# Breadboard.net
KiCad netlist of a schematic drawn in EAGLE
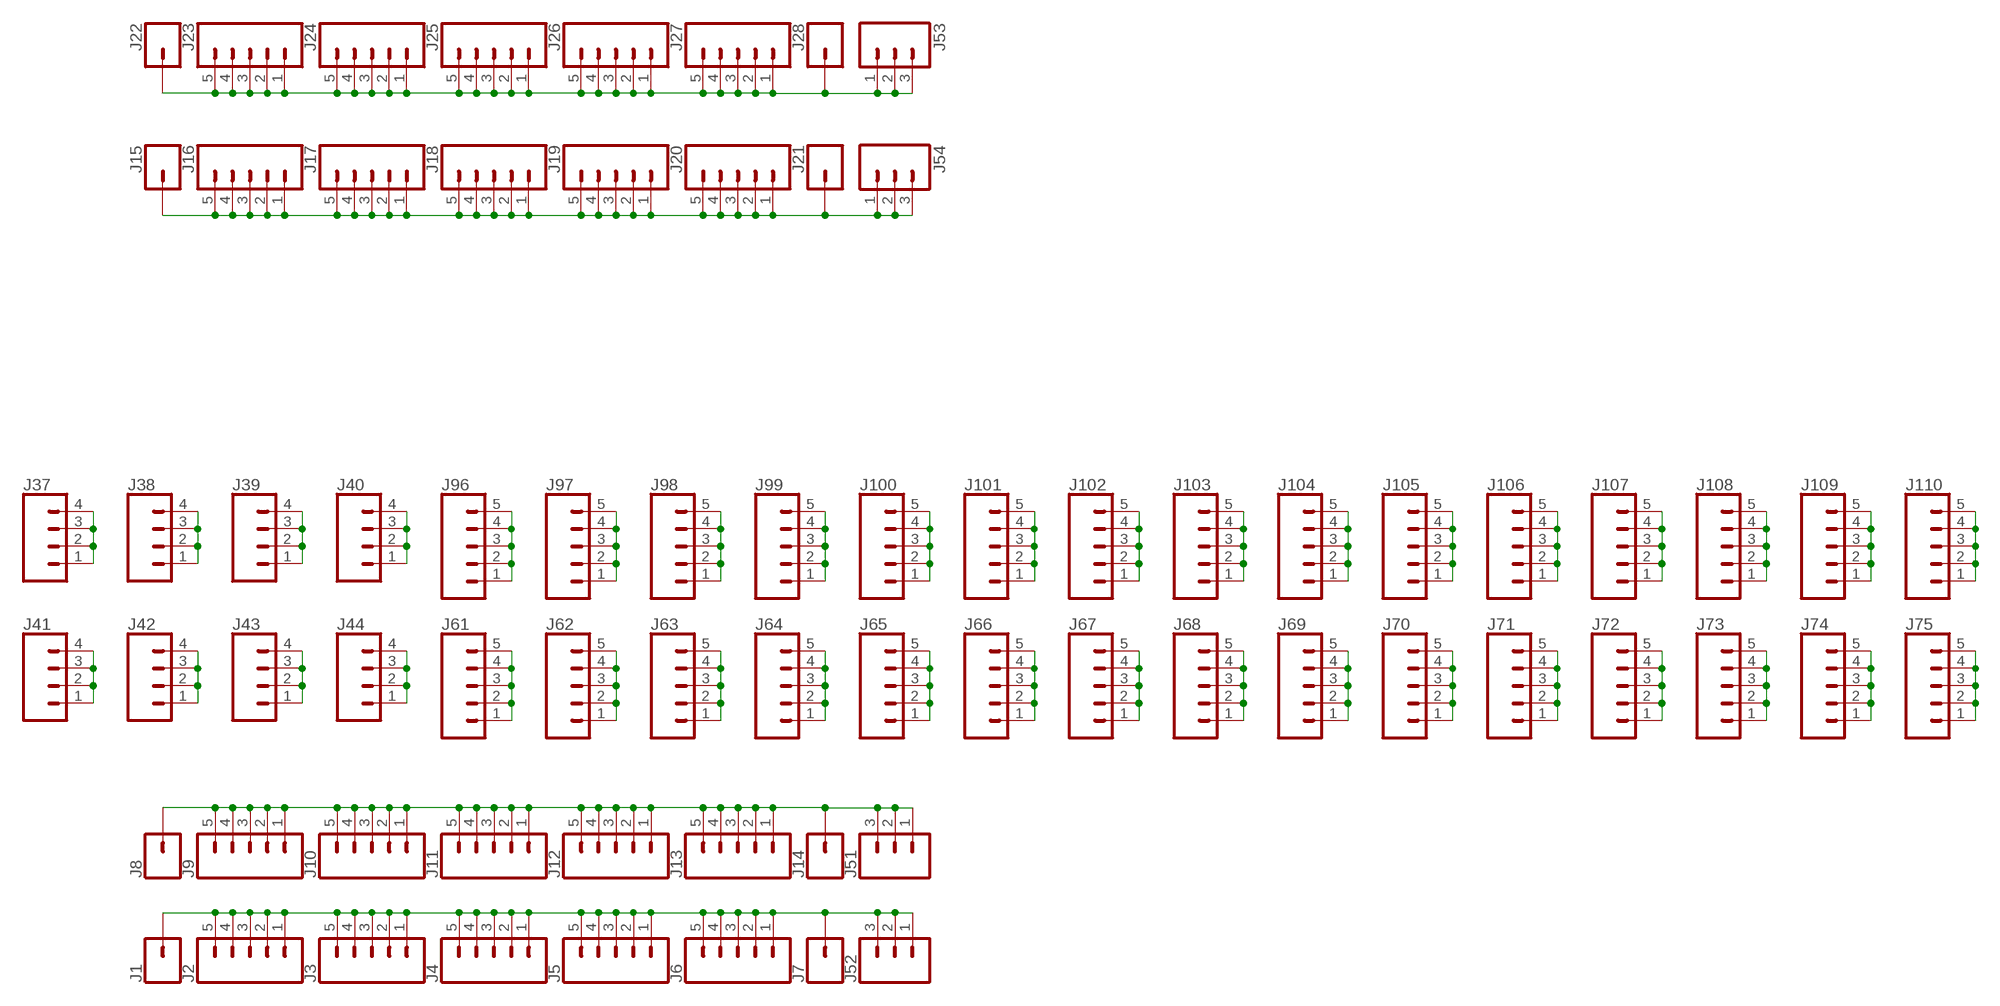
[diagram p0: schematic, sheet 1, part 1 of 2]
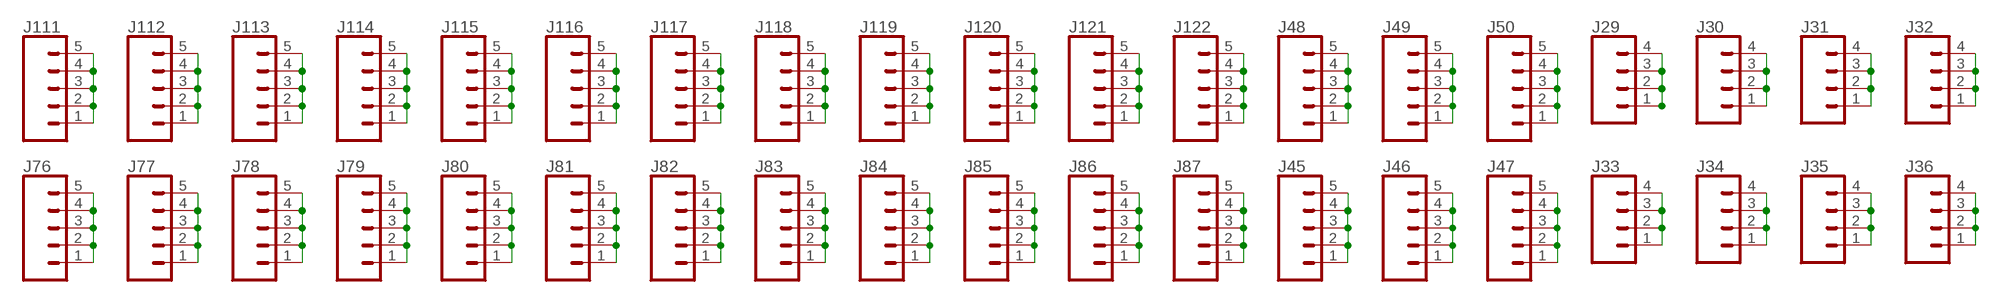
[diagram p1: schematic, sheet 1, part 2 of 2]

(export (version "E")
  (design (tool "Eeschema 10.0.6"))
  (components
    (comp (ref "J1")
      (value "CONN_01")
      (footprint "eagle-import:1X01")
      (libsource (lib "eagle-import") (part "CONN_01"))
    )
    (comp (ref "J2")
      (value "CONN_05")
      (footprint "eagle-import:1X05")
      (libsource (lib "eagle-import") (part "CONN_05"))
    )
    (comp (ref "J3")
      (value "CONN_05")
      (footprint "eagle-import:1X05")
      (libsource (lib "eagle-import") (part "CONN_05"))
    )
    (comp (ref "J4")
      (value "CONN_05")
      (footprint "eagle-import:1X05")
      (libsource (lib "eagle-import") (part "CONN_05"))
    )
    (comp (ref "J5")
      (value "CONN_05")
      (footprint "eagle-import:1X05")
      (libsource (lib "eagle-import") (part "CONN_05"))
    )
    (comp (ref "J6")
      (value "CONN_05")
      (footprint "eagle-import:1X05")
      (libsource (lib "eagle-import") (part "CONN_05"))
    )
    (comp (ref "J7")
      (value "CONN_01")
      (footprint "eagle-import:1X01")
      (libsource (lib "eagle-import") (part "CONN_01"))
    )
    (comp (ref "J8")
      (value "CONN_01")
      (footprint "eagle-import:1X01")
      (libsource (lib "eagle-import") (part "CONN_01"))
    )
    (comp (ref "J9")
      (value "CONN_05")
      (footprint "eagle-import:1X05")
      (libsource (lib "eagle-import") (part "CONN_05"))
    )
    (comp (ref "J10")
      (value "CONN_05")
      (footprint "eagle-import:1X05")
      (libsource (lib "eagle-import") (part "CONN_05"))
    )
    (comp (ref "J11")
      (value "CONN_05")
      (footprint "eagle-import:1X05")
      (libsource (lib "eagle-import") (part "CONN_05"))
    )
    (comp (ref "J12")
      (value "CONN_05")
      (footprint "eagle-import:1X05")
      (libsource (lib "eagle-import") (part "CONN_05"))
    )
    (comp (ref "J13")
      (value "CONN_05")
      (footprint "eagle-import:1X05")
      (libsource (lib "eagle-import") (part "CONN_05"))
    )
    (comp (ref "J14")
      (value "CONN_01")
      (footprint "eagle-import:1X01")
      (libsource (lib "eagle-import") (part "CONN_01"))
    )
    (comp (ref "J15")
      (value "CONN_01")
      (footprint "eagle-import:1X01")
      (libsource (lib "eagle-import") (part "CONN_01"))
    )
    (comp (ref "J16")
      (value "CONN_05")
      (footprint "eagle-import:1X05")
      (libsource (lib "eagle-import") (part "CONN_05"))
    )
    (comp (ref "J17")
      (value "CONN_05")
      (footprint "eagle-import:1X05")
      (libsource (lib "eagle-import") (part "CONN_05"))
    )
    (comp (ref "J18")
      (value "CONN_05")
      (footprint "eagle-import:1X05")
      (libsource (lib "eagle-import") (part "CONN_05"))
    )
    (comp (ref "J19")
      (value "CONN_05")
      (footprint "eagle-import:1X05")
      (libsource (lib "eagle-import") (part "CONN_05"))
    )
    (comp (ref "J20")
      (value "CONN_05")
      (footprint "eagle-import:1X05")
      (libsource (lib "eagle-import") (part "CONN_05"))
    )
    (comp (ref "J21")
      (value "CONN_01")
      (footprint "eagle-import:1X01")
      (libsource (lib "eagle-import") (part "CONN_01"))
    )
    (comp (ref "J22")
      (value "CONN_01")
      (footprint "eagle-import:1X01")
      (libsource (lib "eagle-import") (part "CONN_01"))
    )
    (comp (ref "J23")
      (value "CONN_05")
      (footprint "eagle-import:1X05")
      (libsource (lib "eagle-import") (part "CONN_05"))
    )
    (comp (ref "J24")
      (value "CONN_05")
      (footprint "eagle-import:1X05")
      (libsource (lib "eagle-import") (part "CONN_05"))
    )
    (comp (ref "J25")
      (value "CONN_05")
      (footprint "eagle-import:1X05")
      (libsource (lib "eagle-import") (part "CONN_05"))
    )
    (comp (ref "J26")
      (value "CONN_05")
      (footprint "eagle-import:1X05")
      (libsource (lib "eagle-import") (part "CONN_05"))
    )
    (comp (ref "J27")
      (value "CONN_05")
      (footprint "eagle-import:1X05")
      (libsource (lib "eagle-import") (part "CONN_05"))
    )
    (comp (ref "J28")
      (value "CONN_01")
      (footprint "eagle-import:1X01")
      (libsource (lib "eagle-import") (part "CONN_01"))
    )
    (comp (ref "J29")
      (value "CONN_04PTH")
      (footprint "eagle-import:1X04")
      (libsource (lib "eagle-import") (part "CONN_04PTH"))
    )
    (comp (ref "J30")
      (value "CONN_04PTH")
      (footprint "eagle-import:1X04")
      (libsource (lib "eagle-import") (part "CONN_04PTH"))
    )
    (comp (ref "J31")
      (value "CONN_04PTH")
      (footprint "eagle-import:1X04")
      (libsource (lib "eagle-import") (part "CONN_04PTH"))
    )
    (comp (ref "J32")
      (value "CONN_04PTH")
      (footprint "eagle-import:1X04")
      (libsource (lib "eagle-import") (part "CONN_04PTH"))
    )
    (comp (ref "J33")
      (value "CONN_04PTH")
      (footprint "eagle-import:1X04")
      (libsource (lib "eagle-import") (part "CONN_04PTH"))
    )
    (comp (ref "J34")
      (value "CONN_04PTH")
      (footprint "eagle-import:1X04")
      (libsource (lib "eagle-import") (part "CONN_04PTH"))
    )
    (comp (ref "J35")
      (value "CONN_04PTH")
      (footprint "eagle-import:1X04")
      (libsource (lib "eagle-import") (part "CONN_04PTH"))
    )
    (comp (ref "J36")
      (value "CONN_04PTH")
      (footprint "eagle-import:1X04")
      (libsource (lib "eagle-import") (part "CONN_04PTH"))
    )
    (comp (ref "J37")
      (value "CONN_04PTH")
      (footprint "eagle-import:1X04")
      (libsource (lib "eagle-import") (part "CONN_04PTH"))
    )
    (comp (ref "J38")
      (value "CONN_04PTH")
      (footprint "eagle-import:1X04")
      (libsource (lib "eagle-import") (part "CONN_04PTH"))
    )
    (comp (ref "J39")
      (value "CONN_04PTH")
      (footprint "eagle-import:1X04")
      (libsource (lib "eagle-import") (part "CONN_04PTH"))
    )
    (comp (ref "J40")
      (value "CONN_04PTH")
      (footprint "eagle-import:1X04")
      (libsource (lib "eagle-import") (part "CONN_04PTH"))
    )
    (comp (ref "J41")
      (value "CONN_04PTH")
      (footprint "eagle-import:1X04")
      (libsource (lib "eagle-import") (part "CONN_04PTH"))
    )
    (comp (ref "J42")
      (value "CONN_04PTH")
      (footprint "eagle-import:1X04")
      (libsource (lib "eagle-import") (part "CONN_04PTH"))
    )
    (comp (ref "J43")
      (value "CONN_04PTH")
      (footprint "eagle-import:1X04")
      (libsource (lib "eagle-import") (part "CONN_04PTH"))
    )
    (comp (ref "J44")
      (value "CONN_04PTH")
      (footprint "eagle-import:1X04")
      (libsource (lib "eagle-import") (part "CONN_04PTH"))
    )
    (comp (ref "J45")
      (value "CONN_05")
      (footprint "eagle-import:1X05")
      (libsource (lib "eagle-import") (part "CONN_05"))
    )
    (comp (ref "J46")
      (value "CONN_05")
      (footprint "eagle-import:1X05")
      (libsource (lib "eagle-import") (part "CONN_05"))
    )
    (comp (ref "J47")
      (value "CONN_05")
      (footprint "eagle-import:1X05")
      (libsource (lib "eagle-import") (part "CONN_05"))
    )
    (comp (ref "J48")
      (value "CONN_05")
      (footprint "eagle-import:1X05")
      (libsource (lib "eagle-import") (part "CONN_05"))
    )
    (comp (ref "J49")
      (value "CONN_05")
      (footprint "eagle-import:1X05")
      (libsource (lib "eagle-import") (part "CONN_05"))
    )
    (comp (ref "J50")
      (value "CONN_05")
      (footprint "eagle-import:1X05")
      (libsource (lib "eagle-import") (part "CONN_05"))
    )
    (comp (ref "J51")
      (value "455-1750-1-ND")
      (footprint "eagle-import:1X03")
      (libsource (lib "eagle-import") (part "CONN_03"))
    )
    (comp (ref "J52")
      (value "455-1750-1-ND")
      (footprint "eagle-import:1X03")
      (libsource (lib "eagle-import") (part "CONN_03"))
    )
    (comp (ref "J53")
      (value "455-1750-1-ND")
      (footprint "eagle-import:1X03")
      (libsource (lib "eagle-import") (part "CONN_03"))
    )
    (comp (ref "J54")
      (value "455-1750-1-ND")
      (footprint "eagle-import:1X03")
      (libsource (lib "eagle-import") (part "CONN_03"))
    )
    (comp (ref "J61")
      (value "CONN_05")
      (footprint "eagle-import:1X05")
      (libsource (lib "eagle-import") (part "CONN_05"))
    )
    (comp (ref "J62")
      (value "CONN_05")
      (footprint "eagle-import:1X05")
      (libsource (lib "eagle-import") (part "CONN_05"))
    )
    (comp (ref "J63")
      (value "CONN_05")
      (footprint "eagle-import:1X05")
      (libsource (lib "eagle-import") (part "CONN_05"))
    )
    (comp (ref "J64")
      (value "CONN_05")
      (footprint "eagle-import:1X05")
      (libsource (lib "eagle-import") (part "CONN_05"))
    )
    (comp (ref "J65")
      (value "CONN_05")
      (footprint "eagle-import:1X05")
      (libsource (lib "eagle-import") (part "CONN_05"))
    )
    (comp (ref "J66")
      (value "CONN_05")
      (footprint "eagle-import:1X05")
      (libsource (lib "eagle-import") (part "CONN_05"))
    )
    (comp (ref "J67")
      (value "CONN_05")
      (footprint "eagle-import:1X05")
      (libsource (lib "eagle-import") (part "CONN_05"))
    )
    (comp (ref "J68")
      (value "CONN_05")
      (footprint "eagle-import:1X05")
      (libsource (lib "eagle-import") (part "CONN_05"))
    )
    (comp (ref "J69")
      (value "CONN_05")
      (footprint "eagle-import:1X05")
      (libsource (lib "eagle-import") (part "CONN_05"))
    )
    (comp (ref "J70")
      (value "CONN_05")
      (footprint "eagle-import:1X05")
      (libsource (lib "eagle-import") (part "CONN_05"))
    )
    (comp (ref "J71")
      (value "CONN_05")
      (footprint "eagle-import:1X05")
      (libsource (lib "eagle-import") (part "CONN_05"))
    )
    (comp (ref "J72")
      (value "CONN_05")
      (footprint "eagle-import:1X05")
      (libsource (lib "eagle-import") (part "CONN_05"))
    )
    (comp (ref "J73")
      (value "CONN_05")
      (footprint "eagle-import:1X05")
      (libsource (lib "eagle-import") (part "CONN_05"))
    )
    (comp (ref "J74")
      (value "CONN_05")
      (footprint "eagle-import:1X05")
      (libsource (lib "eagle-import") (part "CONN_05"))
    )
    (comp (ref "J75")
      (value "CONN_05")
      (footprint "eagle-import:1X05")
      (libsource (lib "eagle-import") (part "CONN_05"))
    )
    (comp (ref "J76")
      (value "CONN_05")
      (footprint "eagle-import:1X05")
      (libsource (lib "eagle-import") (part "CONN_05"))
    )
    (comp (ref "J77")
      (value "CONN_05")
      (footprint "eagle-import:1X05")
      (libsource (lib "eagle-import") (part "CONN_05"))
    )
    (comp (ref "J78")
      (value "CONN_05")
      (footprint "eagle-import:1X05")
      (libsource (lib "eagle-import") (part "CONN_05"))
    )
    (comp (ref "J79")
      (value "CONN_05")
      (footprint "eagle-import:1X05")
      (libsource (lib "eagle-import") (part "CONN_05"))
    )
    (comp (ref "J80")
      (value "CONN_05")
      (footprint "eagle-import:1X05")
      (libsource (lib "eagle-import") (part "CONN_05"))
    )
    (comp (ref "J81")
      (value "CONN_05")
      (footprint "eagle-import:1X05")
      (libsource (lib "eagle-import") (part "CONN_05"))
    )
    (comp (ref "J82")
      (value "CONN_05")
      (footprint "eagle-import:1X05")
      (libsource (lib "eagle-import") (part "CONN_05"))
    )
    (comp (ref "J83")
      (value "CONN_05")
      (footprint "eagle-import:1X05")
      (libsource (lib "eagle-import") (part "CONN_05"))
    )
    (comp (ref "J84")
      (value "CONN_05")
      (footprint "eagle-import:1X05")
      (libsource (lib "eagle-import") (part "CONN_05"))
    )
    (comp (ref "J85")
      (value "CONN_05")
      (footprint "eagle-import:1X05")
      (libsource (lib "eagle-import") (part "CONN_05"))
    )
    (comp (ref "J86")
      (value "CONN_05")
      (footprint "eagle-import:1X05")
      (libsource (lib "eagle-import") (part "CONN_05"))
    )
    (comp (ref "J87")
      (value "CONN_05")
      (footprint "eagle-import:1X05")
      (libsource (lib "eagle-import") (part "CONN_05"))
    )
    (comp (ref "J96")
      (value "CONN_05")
      (footprint "eagle-import:1X05")
      (libsource (lib "eagle-import") (part "CONN_05"))
    )
    (comp (ref "J97")
      (value "CONN_05")
      (footprint "eagle-import:1X05")
      (libsource (lib "eagle-import") (part "CONN_05"))
    )
    (comp (ref "J98")
      (value "CONN_05")
      (footprint "eagle-import:1X05")
      (libsource (lib "eagle-import") (part "CONN_05"))
    )
    (comp (ref "J99")
      (value "CONN_05")
      (footprint "eagle-import:1X05")
      (libsource (lib "eagle-import") (part "CONN_05"))
    )
    (comp (ref "J100")
      (value "CONN_05")
      (footprint "eagle-import:1X05")
      (libsource (lib "eagle-import") (part "CONN_05"))
    )
    (comp (ref "J101")
      (value "CONN_05")
      (footprint "eagle-import:1X05")
      (libsource (lib "eagle-import") (part "CONN_05"))
    )
    (comp (ref "J102")
      (value "CONN_05")
      (footprint "eagle-import:1X05")
      (libsource (lib "eagle-import") (part "CONN_05"))
    )
    (comp (ref "J103")
      (value "CONN_05")
      (footprint "eagle-import:1X05")
      (libsource (lib "eagle-import") (part "CONN_05"))
    )
    (comp (ref "J104")
      (value "CONN_05")
      (footprint "eagle-import:1X05")
      (libsource (lib "eagle-import") (part "CONN_05"))
    )
    (comp (ref "J105")
      (value "CONN_05")
      (footprint "eagle-import:1X05")
      (libsource (lib "eagle-import") (part "CONN_05"))
    )
    (comp (ref "J106")
      (value "CONN_05")
      (footprint "eagle-import:1X05")
      (libsource (lib "eagle-import") (part "CONN_05"))
    )
    (comp (ref "J107")
      (value "CONN_05")
      (footprint "eagle-import:1X05")
      (libsource (lib "eagle-import") (part "CONN_05"))
    )
    (comp (ref "J108")
      (value "CONN_05")
      (footprint "eagle-import:1X05")
      (libsource (lib "eagle-import") (part "CONN_05"))
    )
    (comp (ref "J109")
      (value "CONN_05")
      (footprint "eagle-import:1X05")
      (libsource (lib "eagle-import") (part "CONN_05"))
    )
    (comp (ref "J110")
      (value "CONN_05")
      (footprint "eagle-import:1X05")
      (libsource (lib "eagle-import") (part "CONN_05"))
    )
    (comp (ref "J111")
      (value "CONN_05")
      (footprint "eagle-import:1X05")
      (libsource (lib "eagle-import") (part "CONN_05"))
    )
    (comp (ref "J112")
      (value "CONN_05")
      (footprint "eagle-import:1X05")
      (libsource (lib "eagle-import") (part "CONN_05"))
    )
    (comp (ref "J113")
      (value "CONN_05")
      (footprint "eagle-import:1X05")
      (libsource (lib "eagle-import") (part "CONN_05"))
    )
    (comp (ref "J114")
      (value "CONN_05")
      (footprint "eagle-import:1X05")
      (libsource (lib "eagle-import") (part "CONN_05"))
    )
    (comp (ref "J115")
      (value "CONN_05")
      (footprint "eagle-import:1X05")
      (libsource (lib "eagle-import") (part "CONN_05"))
    )
    (comp (ref "J116")
      (value "CONN_05")
      (footprint "eagle-import:1X05")
      (libsource (lib "eagle-import") (part "CONN_05"))
    )
    (comp (ref "J117")
      (value "CONN_05")
      (footprint "eagle-import:1X05")
      (libsource (lib "eagle-import") (part "CONN_05"))
    )
    (comp (ref "J118")
      (value "CONN_05")
      (footprint "eagle-import:1X05")
      (libsource (lib "eagle-import") (part "CONN_05"))
    )
    (comp (ref "J119")
      (value "CONN_05")
      (footprint "eagle-import:1X05")
      (libsource (lib "eagle-import") (part "CONN_05"))
    )
    (comp (ref "J120")
      (value "CONN_05")
      (footprint "eagle-import:1X05")
      (libsource (lib "eagle-import") (part "CONN_05"))
    )
    (comp (ref "J121")
      (value "CONN_05")
      (footprint "eagle-import:1X05")
      (libsource (lib "eagle-import") (part "CONN_05"))
    )
    (comp (ref "J122")
      (value "CONN_05")
      (footprint "eagle-import:1X05")
      (libsource (lib "eagle-import") (part "CONN_05"))
    )
  )
  (nets
    (net (code "1") (name "Net-(J1-Pad1)") (class "Default")
      (node (ref "J1") (pin "1") (pinfunction "1_1") (pintype "passive"))
      (node (ref "J2") (pin "1") (pinfunction "1_1") (pintype "passive"))
      (node (ref "J2") (pin "2") (pinfunction "2_2") (pintype "passive"))
      (node (ref "J2") (pin "3") (pinfunction "3_3") (pintype "passive"))
      (node (ref "J2") (pin "4") (pinfunction "4_4") (pintype "passive"))
      (node (ref "J2") (pin "5") (pinfunction "5_5") (pintype "passive"))
      (node (ref "J3") (pin "1") (pinfunction "1_1") (pintype "passive"))
      (node (ref "J3") (pin "2") (pinfunction "2_2") (pintype "passive"))
      (node (ref "J3") (pin "3") (pinfunction "3_3") (pintype "passive"))
      (node (ref "J3") (pin "4") (pinfunction "4_4") (pintype "passive"))
      (node (ref "J3") (pin "5") (pinfunction "5_5") (pintype "passive"))
      (node (ref "J4") (pin "1") (pinfunction "1_1") (pintype "passive"))
      (node (ref "J4") (pin "2") (pinfunction "2_2") (pintype "passive"))
      (node (ref "J4") (pin "3") (pinfunction "3_3") (pintype "passive"))
      (node (ref "J4") (pin "4") (pinfunction "4_4") (pintype "passive"))
      (node (ref "J4") (pin "5") (pinfunction "5_5") (pintype "passive"))
      (node (ref "J5") (pin "1") (pinfunction "1_1") (pintype "passive"))
      (node (ref "J5") (pin "2") (pinfunction "2_2") (pintype "passive"))
      (node (ref "J5") (pin "3") (pinfunction "3_3") (pintype "passive"))
      (node (ref "J5") (pin "4") (pinfunction "4_4") (pintype "passive"))
      (node (ref "J5") (pin "5") (pinfunction "5_5") (pintype "passive"))
      (node (ref "J52") (pin "1") (pinfunction "1_1") (pintype "passive"))
      (node (ref "J52") (pin "2") (pinfunction "2_2") (pintype "passive"))
      (node (ref "J52") (pin "3") (pinfunction "3_3") (pintype "passive"))
      (node (ref "J6") (pin "1") (pinfunction "1_1") (pintype "passive"))
      (node (ref "J6") (pin "2") (pinfunction "2_2") (pintype "passive"))
      (node (ref "J6") (pin "3") (pinfunction "3_3") (pintype "passive"))
      (node (ref "J6") (pin "4") (pinfunction "4_4") (pintype "passive"))
      (node (ref "J6") (pin "5") (pinfunction "5_5") (pintype "passive"))
      (node (ref "J7") (pin "1") (pinfunction "1_1") (pintype "passive"))
    )
    (net (code "2") (name "Net-(J10-Pad1)") (class "Default")
      (node (ref "J10") (pin "1") (pinfunction "1_1") (pintype "passive"))
      (node (ref "J10") (pin "2") (pinfunction "2_2") (pintype "passive"))
      (node (ref "J10") (pin "3") (pinfunction "3_3") (pintype "passive"))
      (node (ref "J10") (pin "4") (pinfunction "4_4") (pintype "passive"))
      (node (ref "J10") (pin "5") (pinfunction "5_5") (pintype "passive"))
      (node (ref "J11") (pin "1") (pinfunction "1_1") (pintype "passive"))
      (node (ref "J11") (pin "2") (pinfunction "2_2") (pintype "passive"))
      (node (ref "J11") (pin "3") (pinfunction "3_3") (pintype "passive"))
      (node (ref "J11") (pin "4") (pinfunction "4_4") (pintype "passive"))
      (node (ref "J11") (pin "5") (pinfunction "5_5") (pintype "passive"))
      (node (ref "J12") (pin "1") (pinfunction "1_1") (pintype "passive"))
      (node (ref "J12") (pin "2") (pinfunction "2_2") (pintype "passive"))
      (node (ref "J12") (pin "3") (pinfunction "3_3") (pintype "passive"))
      (node (ref "J12") (pin "4") (pinfunction "4_4") (pintype "passive"))
      (node (ref "J12") (pin "5") (pinfunction "5_5") (pintype "passive"))
      (node (ref "J13") (pin "1") (pinfunction "1_1") (pintype "passive"))
      (node (ref "J13") (pin "2") (pinfunction "2_2") (pintype "passive"))
      (node (ref "J13") (pin "3") (pinfunction "3_3") (pintype "passive"))
      (node (ref "J13") (pin "4") (pinfunction "4_4") (pintype "passive"))
      (node (ref "J13") (pin "5") (pinfunction "5_5") (pintype "passive"))
      (node (ref "J14") (pin "1") (pinfunction "1_1") (pintype "passive"))
      (node (ref "J51") (pin "1") (pinfunction "1_1") (pintype "passive"))
      (node (ref "J51") (pin "2") (pinfunction "2_2") (pintype "passive"))
      (node (ref "J51") (pin "3") (pinfunction "3_3") (pintype "passive"))
      (node (ref "J8") (pin "1") (pinfunction "1_1") (pintype "passive"))
      (node (ref "J9") (pin "1") (pinfunction "1_1") (pintype "passive"))
      (node (ref "J9") (pin "2") (pinfunction "2_2") (pintype "passive"))
      (node (ref "J9") (pin "3") (pinfunction "3_3") (pintype "passive"))
      (node (ref "J9") (pin "4") (pinfunction "4_4") (pintype "passive"))
      (node (ref "J9") (pin "5") (pinfunction "5_5") (pintype "passive"))
    )
    (net (code "3") (name "Net-(J15-Pad1)") (class "Default")
      (node (ref "J15") (pin "1") (pinfunction "1_1") (pintype "passive"))
      (node (ref "J16") (pin "1") (pinfunction "1_1") (pintype "passive"))
      (node (ref "J16") (pin "2") (pinfunction "2_2") (pintype "passive"))
      (node (ref "J16") (pin "3") (pinfunction "3_3") (pintype "passive"))
      (node (ref "J16") (pin "4") (pinfunction "4_4") (pintype "passive"))
      (node (ref "J16") (pin "5") (pinfunction "5_5") (pintype "passive"))
      (node (ref "J17") (pin "1") (pinfunction "1_1") (pintype "passive"))
      (node (ref "J17") (pin "2") (pinfunction "2_2") (pintype "passive"))
      (node (ref "J17") (pin "3") (pinfunction "3_3") (pintype "passive"))
      (node (ref "J17") (pin "4") (pinfunction "4_4") (pintype "passive"))
      (node (ref "J17") (pin "5") (pinfunction "5_5") (pintype "passive"))
      (node (ref "J18") (pin "1") (pinfunction "1_1") (pintype "passive"))
      (node (ref "J18") (pin "2") (pinfunction "2_2") (pintype "passive"))
      (node (ref "J18") (pin "3") (pinfunction "3_3") (pintype "passive"))
      (node (ref "J18") (pin "4") (pinfunction "4_4") (pintype "passive"))
      (node (ref "J18") (pin "5") (pinfunction "5_5") (pintype "passive"))
      (node (ref "J19") (pin "1") (pinfunction "1_1") (pintype "passive"))
      (node (ref "J19") (pin "2") (pinfunction "2_2") (pintype "passive"))
      (node (ref "J19") (pin "3") (pinfunction "3_3") (pintype "passive"))
      (node (ref "J19") (pin "4") (pinfunction "4_4") (pintype "passive"))
      (node (ref "J19") (pin "5") (pinfunction "5_5") (pintype "passive"))
      (node (ref "J20") (pin "1") (pinfunction "1_1") (pintype "passive"))
      (node (ref "J20") (pin "2") (pinfunction "2_2") (pintype "passive"))
      (node (ref "J20") (pin "3") (pinfunction "3_3") (pintype "passive"))
      (node (ref "J20") (pin "4") (pinfunction "4_4") (pintype "passive"))
      (node (ref "J20") (pin "5") (pinfunction "5_5") (pintype "passive"))
      (node (ref "J21") (pin "1") (pinfunction "1_1") (pintype "passive"))
      (node (ref "J54") (pin "1") (pinfunction "1_1") (pintype "passive"))
      (node (ref "J54") (pin "2") (pinfunction "2_2") (pintype "passive"))
      (node (ref "J54") (pin "3") (pinfunction "3_3") (pintype "passive"))
    )
    (net (code "4") (name "Net-(J22-Pad1)") (class "Default")
      (node (ref "J22") (pin "1") (pinfunction "1_1") (pintype "passive"))
      (node (ref "J23") (pin "1") (pinfunction "1_1") (pintype "passive"))
      (node (ref "J23") (pin "2") (pinfunction "2_2") (pintype "passive"))
      (node (ref "J23") (pin "3") (pinfunction "3_3") (pintype "passive"))
      (node (ref "J23") (pin "4") (pinfunction "4_4") (pintype "passive"))
      (node (ref "J23") (pin "5") (pinfunction "5_5") (pintype "passive"))
      (node (ref "J24") (pin "1") (pinfunction "1_1") (pintype "passive"))
      (node (ref "J24") (pin "2") (pinfunction "2_2") (pintype "passive"))
      (node (ref "J24") (pin "3") (pinfunction "3_3") (pintype "passive"))
      (node (ref "J24") (pin "4") (pinfunction "4_4") (pintype "passive"))
      (node (ref "J24") (pin "5") (pinfunction "5_5") (pintype "passive"))
      (node (ref "J25") (pin "1") (pinfunction "1_1") (pintype "passive"))
      (node (ref "J25") (pin "2") (pinfunction "2_2") (pintype "passive"))
      (node (ref "J25") (pin "3") (pinfunction "3_3") (pintype "passive"))
      (node (ref "J25") (pin "4") (pinfunction "4_4") (pintype "passive"))
      (node (ref "J25") (pin "5") (pinfunction "5_5") (pintype "passive"))
      (node (ref "J26") (pin "1") (pinfunction "1_1") (pintype "passive"))
      (node (ref "J26") (pin "2") (pinfunction "2_2") (pintype "passive"))
      (node (ref "J26") (pin "3") (pinfunction "3_3") (pintype "passive"))
      (node (ref "J26") (pin "4") (pinfunction "4_4") (pintype "passive"))
      (node (ref "J26") (pin "5") (pinfunction "5_5") (pintype "passive"))
      (node (ref "J27") (pin "1") (pinfunction "1_1") (pintype "passive"))
      (node (ref "J27") (pin "2") (pinfunction "2_2") (pintype "passive"))
      (node (ref "J27") (pin "3") (pinfunction "3_3") (pintype "passive"))
      (node (ref "J27") (pin "4") (pinfunction "4_4") (pintype "passive"))
      (node (ref "J27") (pin "5") (pinfunction "5_5") (pintype "passive"))
      (node (ref "J28") (pin "1") (pinfunction "1_1") (pintype "passive"))
      (node (ref "J53") (pin "1") (pinfunction "1_1") (pintype "passive"))
      (node (ref "J53") (pin "2") (pinfunction "2_2") (pintype "passive"))
      (node (ref "J53") (pin "3") (pinfunction "3_3") (pintype "passive"))
    )
    (net (code "5") (name "Net-(J29-Pad1)") (class "Default")
      (node (ref "J29") (pin "1") (pinfunction "1_1") (pintype "passive"))
      (node (ref "J29") (pin "2") (pinfunction "2_2") (pintype "passive"))
      (node (ref "J29") (pin "3") (pinfunction "3_3") (pintype "passive"))
      (node (ref "J29") (pin "4") (pinfunction "4_4") (pintype "passive"))
    )
    (net (code "6") (name "Net-(J30-Pad1)") (class "Default")
      (node (ref "J30") (pin "1") (pinfunction "1_1") (pintype "passive"))
      (node (ref "J30") (pin "2") (pinfunction "2_2") (pintype "passive"))
      (node (ref "J30") (pin "3") (pinfunction "3_3") (pintype "passive"))
      (node (ref "J30") (pin "4") (pinfunction "4_4") (pintype "passive"))
    )
    (net (code "7") (name "Net-(J31-Pad1)") (class "Default")
      (node (ref "J31") (pin "1") (pinfunction "1_1") (pintype "passive"))
      (node (ref "J31") (pin "2") (pinfunction "2_2") (pintype "passive"))
      (node (ref "J31") (pin "3") (pinfunction "3_3") (pintype "passive"))
      (node (ref "J31") (pin "4") (pinfunction "4_4") (pintype "passive"))
    )
    (net (code "8") (name "Net-(J32-Pad1)") (class "Default")
      (node (ref "J32") (pin "1") (pinfunction "1_1") (pintype "passive"))
      (node (ref "J32") (pin "2") (pinfunction "2_2") (pintype "passive"))
      (node (ref "J32") (pin "3") (pinfunction "3_3") (pintype "passive"))
      (node (ref "J32") (pin "4") (pinfunction "4_4") (pintype "passive"))
    )
    (net (code "9") (name "Net-(J33-Pad1)") (class "Default")
      (node (ref "J33") (pin "1") (pinfunction "1_1") (pintype "passive"))
      (node (ref "J33") (pin "2") (pinfunction "2_2") (pintype "passive"))
      (node (ref "J33") (pin "3") (pinfunction "3_3") (pintype "passive"))
      (node (ref "J33") (pin "4") (pinfunction "4_4") (pintype "passive"))
    )
    (net (code "10") (name "Net-(J34-Pad1)") (class "Default")
      (node (ref "J34") (pin "1") (pinfunction "1_1") (pintype "passive"))
      (node (ref "J34") (pin "2") (pinfunction "2_2") (pintype "passive"))
      (node (ref "J34") (pin "3") (pinfunction "3_3") (pintype "passive"))
      (node (ref "J34") (pin "4") (pinfunction "4_4") (pintype "passive"))
    )
    (net (code "11") (name "Net-(J35-Pad1)") (class "Default")
      (node (ref "J35") (pin "1") (pinfunction "1_1") (pintype "passive"))
      (node (ref "J35") (pin "2") (pinfunction "2_2") (pintype "passive"))
      (node (ref "J35") (pin "3") (pinfunction "3_3") (pintype "passive"))
      (node (ref "J35") (pin "4") (pinfunction "4_4") (pintype "passive"))
    )
    (net (code "12") (name "Net-(J36-Pad1)") (class "Default")
      (node (ref "J36") (pin "1") (pinfunction "1_1") (pintype "passive"))
      (node (ref "J36") (pin "2") (pinfunction "2_2") (pintype "passive"))
      (node (ref "J36") (pin "3") (pinfunction "3_3") (pintype "passive"))
      (node (ref "J36") (pin "4") (pinfunction "4_4") (pintype "passive"))
    )
    (net (code "13") (name "Net-(J37-Pad1)") (class "Default")
      (node (ref "J37") (pin "1") (pinfunction "1_1") (pintype "passive"))
      (node (ref "J37") (pin "2") (pinfunction "2_2") (pintype "passive"))
      (node (ref "J37") (pin "3") (pinfunction "3_3") (pintype "passive"))
      (node (ref "J37") (pin "4") (pinfunction "4_4") (pintype "passive"))
    )
    (net (code "14") (name "Net-(J38-Pad1)") (class "Default")
      (node (ref "J38") (pin "1") (pinfunction "1_1") (pintype "passive"))
      (node (ref "J38") (pin "2") (pinfunction "2_2") (pintype "passive"))
      (node (ref "J38") (pin "3") (pinfunction "3_3") (pintype "passive"))
      (node (ref "J38") (pin "4") (pinfunction "4_4") (pintype "passive"))
    )
    (net (code "15") (name "Net-(J39-Pad1)") (class "Default")
      (node (ref "J39") (pin "1") (pinfunction "1_1") (pintype "passive"))
      (node (ref "J39") (pin "2") (pinfunction "2_2") (pintype "passive"))
      (node (ref "J39") (pin "3") (pinfunction "3_3") (pintype "passive"))
      (node (ref "J39") (pin "4") (pinfunction "4_4") (pintype "passive"))
    )
    (net (code "16") (name "Net-(J40-Pad1)") (class "Default")
      (node (ref "J40") (pin "1") (pinfunction "1_1") (pintype "passive"))
      (node (ref "J40") (pin "2") (pinfunction "2_2") (pintype "passive"))
      (node (ref "J40") (pin "3") (pinfunction "3_3") (pintype "passive"))
      (node (ref "J40") (pin "4") (pinfunction "4_4") (pintype "passive"))
    )
    (net (code "17") (name "Net-(J41-Pad1)") (class "Default")
      (node (ref "J41") (pin "1") (pinfunction "1_1") (pintype "passive"))
      (node (ref "J41") (pin "2") (pinfunction "2_2") (pintype "passive"))
      (node (ref "J41") (pin "3") (pinfunction "3_3") (pintype "passive"))
      (node (ref "J41") (pin "4") (pinfunction "4_4") (pintype "passive"))
    )
    (net (code "18") (name "Net-(J42-Pad1)") (class "Default")
      (node (ref "J42") (pin "1") (pinfunction "1_1") (pintype "passive"))
      (node (ref "J42") (pin "2") (pinfunction "2_2") (pintype "passive"))
      (node (ref "J42") (pin "3") (pinfunction "3_3") (pintype "passive"))
      (node (ref "J42") (pin "4") (pinfunction "4_4") (pintype "passive"))
    )
    (net (code "19") (name "Net-(J43-Pad1)") (class "Default")
      (node (ref "J43") (pin "1") (pinfunction "1_1") (pintype "passive"))
      (node (ref "J43") (pin "2") (pinfunction "2_2") (pintype "passive"))
      (node (ref "J43") (pin "3") (pinfunction "3_3") (pintype "passive"))
      (node (ref "J43") (pin "4") (pinfunction "4_4") (pintype "passive"))
    )
    (net (code "20") (name "Net-(J44-Pad1)") (class "Default")
      (node (ref "J44") (pin "1") (pinfunction "1_1") (pintype "passive"))
      (node (ref "J44") (pin "2") (pinfunction "2_2") (pintype "passive"))
      (node (ref "J44") (pin "3") (pinfunction "3_3") (pintype "passive"))
      (node (ref "J44") (pin "4") (pinfunction "4_4") (pintype "passive"))
    )
    (net (code "21") (name "Net-(J45-Pad1)") (class "Default")
      (node (ref "J45") (pin "1") (pinfunction "1_1") (pintype "passive"))
      (node (ref "J45") (pin "2") (pinfunction "2_2") (pintype "passive"))
      (node (ref "J45") (pin "3") (pinfunction "3_3") (pintype "passive"))
      (node (ref "J45") (pin "4") (pinfunction "4_4") (pintype "passive"))
      (node (ref "J45") (pin "5") (pinfunction "5_5") (pintype "passive"))
    )
    (net (code "22") (name "Net-(J46-Pad1)") (class "Default")
      (node (ref "J46") (pin "1") (pinfunction "1_1") (pintype "passive"))
      (node (ref "J46") (pin "2") (pinfunction "2_2") (pintype "passive"))
      (node (ref "J46") (pin "3") (pinfunction "3_3") (pintype "passive"))
      (node (ref "J46") (pin "4") (pinfunction "4_4") (pintype "passive"))
      (node (ref "J46") (pin "5") (pinfunction "5_5") (pintype "passive"))
    )
    (net (code "23") (name "Net-(J47-Pad1)") (class "Default")
      (node (ref "J47") (pin "1") (pinfunction "1_1") (pintype "passive"))
      (node (ref "J47") (pin "2") (pinfunction "2_2") (pintype "passive"))
      (node (ref "J47") (pin "3") (pinfunction "3_3") (pintype "passive"))
      (node (ref "J47") (pin "4") (pinfunction "4_4") (pintype "passive"))
      (node (ref "J47") (pin "5") (pinfunction "5_5") (pintype "passive"))
    )
    (net (code "24") (name "Net-(J48-Pad1)") (class "Default")
      (node (ref "J48") (pin "1") (pinfunction "1_1") (pintype "passive"))
      (node (ref "J48") (pin "2") (pinfunction "2_2") (pintype "passive"))
      (node (ref "J48") (pin "3") (pinfunction "3_3") (pintype "passive"))
      (node (ref "J48") (pin "4") (pinfunction "4_4") (pintype "passive"))
      (node (ref "J48") (pin "5") (pinfunction "5_5") (pintype "passive"))
    )
    (net (code "25") (name "Net-(J49-Pad1)") (class "Default")
      (node (ref "J49") (pin "1") (pinfunction "1_1") (pintype "passive"))
      (node (ref "J49") (pin "2") (pinfunction "2_2") (pintype "passive"))
      (node (ref "J49") (pin "3") (pinfunction "3_3") (pintype "passive"))
      (node (ref "J49") (pin "4") (pinfunction "4_4") (pintype "passive"))
      (node (ref "J49") (pin "5") (pinfunction "5_5") (pintype "passive"))
    )
    (net (code "26") (name "Net-(J50-Pad1)") (class "Default")
      (node (ref "J50") (pin "1") (pinfunction "1_1") (pintype "passive"))
      (node (ref "J50") (pin "2") (pinfunction "2_2") (pintype "passive"))
      (node (ref "J50") (pin "3") (pinfunction "3_3") (pintype "passive"))
      (node (ref "J50") (pin "4") (pinfunction "4_4") (pintype "passive"))
      (node (ref "J50") (pin "5") (pinfunction "5_5") (pintype "passive"))
    )
    (net (code "27") (name "Net-(J61-Pad1)") (class "Default")
      (node (ref "J61") (pin "1") (pinfunction "1_1") (pintype "passive"))
      (node (ref "J61") (pin "2") (pinfunction "2_2") (pintype "passive"))
      (node (ref "J61") (pin "3") (pinfunction "3_3") (pintype "passive"))
      (node (ref "J61") (pin "4") (pinfunction "4_4") (pintype "passive"))
      (node (ref "J61") (pin "5") (pinfunction "5_5") (pintype "passive"))
    )
    (net (code "28") (name "Net-(J62-Pad1)") (class "Default")
      (node (ref "J62") (pin "1") (pinfunction "1_1") (pintype "passive"))
      (node (ref "J62") (pin "2") (pinfunction "2_2") (pintype "passive"))
      (node (ref "J62") (pin "3") (pinfunction "3_3") (pintype "passive"))
      (node (ref "J62") (pin "4") (pinfunction "4_4") (pintype "passive"))
      (node (ref "J62") (pin "5") (pinfunction "5_5") (pintype "passive"))
    )
    (net (code "29") (name "Net-(J63-Pad1)") (class "Default")
      (node (ref "J63") (pin "1") (pinfunction "1_1") (pintype "passive"))
      (node (ref "J63") (pin "2") (pinfunction "2_2") (pintype "passive"))
      (node (ref "J63") (pin "3") (pinfunction "3_3") (pintype "passive"))
      (node (ref "J63") (pin "4") (pinfunction "4_4") (pintype "passive"))
      (node (ref "J63") (pin "5") (pinfunction "5_5") (pintype "passive"))
    )
    (net (code "30") (name "Net-(J64-Pad1)") (class "Default")
      (node (ref "J64") (pin "1") (pinfunction "1_1") (pintype "passive"))
      (node (ref "J64") (pin "2") (pinfunction "2_2") (pintype "passive"))
      (node (ref "J64") (pin "3") (pinfunction "3_3") (pintype "passive"))
      (node (ref "J64") (pin "4") (pinfunction "4_4") (pintype "passive"))
      (node (ref "J64") (pin "5") (pinfunction "5_5") (pintype "passive"))
    )
    (net (code "31") (name "Net-(J65-Pad1)") (class "Default")
      (node (ref "J65") (pin "1") (pinfunction "1_1") (pintype "passive"))
      (node (ref "J65") (pin "2") (pinfunction "2_2") (pintype "passive"))
      (node (ref "J65") (pin "3") (pinfunction "3_3") (pintype "passive"))
      (node (ref "J65") (pin "4") (pinfunction "4_4") (pintype "passive"))
      (node (ref "J65") (pin "5") (pinfunction "5_5") (pintype "passive"))
    )
    (net (code "32") (name "Net-(J66-Pad1)") (class "Default")
      (node (ref "J66") (pin "1") (pinfunction "1_1") (pintype "passive"))
      (node (ref "J66") (pin "2") (pinfunction "2_2") (pintype "passive"))
      (node (ref "J66") (pin "3") (pinfunction "3_3") (pintype "passive"))
      (node (ref "J66") (pin "4") (pinfunction "4_4") (pintype "passive"))
      (node (ref "J66") (pin "5") (pinfunction "5_5") (pintype "passive"))
    )
    (net (code "33") (name "Net-(J67-Pad1)") (class "Default")
      (node (ref "J67") (pin "1") (pinfunction "1_1") (pintype "passive"))
      (node (ref "J67") (pin "2") (pinfunction "2_2") (pintype "passive"))
      (node (ref "J67") (pin "3") (pinfunction "3_3") (pintype "passive"))
      (node (ref "J67") (pin "4") (pinfunction "4_4") (pintype "passive"))
      (node (ref "J67") (pin "5") (pinfunction "5_5") (pintype "passive"))
    )
    (net (code "34") (name "Net-(J68-Pad1)") (class "Default")
      (node (ref "J68") (pin "1") (pinfunction "1_1") (pintype "passive"))
      (node (ref "J68") (pin "2") (pinfunction "2_2") (pintype "passive"))
      (node (ref "J68") (pin "3") (pinfunction "3_3") (pintype "passive"))
      (node (ref "J68") (pin "4") (pinfunction "4_4") (pintype "passive"))
      (node (ref "J68") (pin "5") (pinfunction "5_5") (pintype "passive"))
    )
    (net (code "35") (name "Net-(J69-Pad1)") (class "Default")
      (node (ref "J69") (pin "1") (pinfunction "1_1") (pintype "passive"))
      (node (ref "J69") (pin "2") (pinfunction "2_2") (pintype "passive"))
      (node (ref "J69") (pin "3") (pinfunction "3_3") (pintype "passive"))
      (node (ref "J69") (pin "4") (pinfunction "4_4") (pintype "passive"))
      (node (ref "J69") (pin "5") (pinfunction "5_5") (pintype "passive"))
    )
    (net (code "36") (name "Net-(J70-Pad1)") (class "Default")
      (node (ref "J70") (pin "1") (pinfunction "1_1") (pintype "passive"))
      (node (ref "J70") (pin "2") (pinfunction "2_2") (pintype "passive"))
      (node (ref "J70") (pin "3") (pinfunction "3_3") (pintype "passive"))
      (node (ref "J70") (pin "4") (pinfunction "4_4") (pintype "passive"))
      (node (ref "J70") (pin "5") (pinfunction "5_5") (pintype "passive"))
    )
    (net (code "37") (name "Net-(J71-Pad1)") (class "Default")
      (node (ref "J71") (pin "1") (pinfunction "1_1") (pintype "passive"))
      (node (ref "J71") (pin "2") (pinfunction "2_2") (pintype "passive"))
      (node (ref "J71") (pin "3") (pinfunction "3_3") (pintype "passive"))
      (node (ref "J71") (pin "4") (pinfunction "4_4") (pintype "passive"))
      (node (ref "J71") (pin "5") (pinfunction "5_5") (pintype "passive"))
    )
    (net (code "38") (name "Net-(J72-Pad1)") (class "Default")
      (node (ref "J72") (pin "1") (pinfunction "1_1") (pintype "passive"))
      (node (ref "J72") (pin "2") (pinfunction "2_2") (pintype "passive"))
      (node (ref "J72") (pin "3") (pinfunction "3_3") (pintype "passive"))
      (node (ref "J72") (pin "4") (pinfunction "4_4") (pintype "passive"))
      (node (ref "J72") (pin "5") (pinfunction "5_5") (pintype "passive"))
    )
    (net (code "39") (name "Net-(J73-Pad1)") (class "Default")
      (node (ref "J73") (pin "1") (pinfunction "1_1") (pintype "passive"))
      (node (ref "J73") (pin "2") (pinfunction "2_2") (pintype "passive"))
      (node (ref "J73") (pin "3") (pinfunction "3_3") (pintype "passive"))
      (node (ref "J73") (pin "4") (pinfunction "4_4") (pintype "passive"))
      (node (ref "J73") (pin "5") (pinfunction "5_5") (pintype "passive"))
    )
    (net (code "40") (name "Net-(J74-Pad1)") (class "Default")
      (node (ref "J74") (pin "1") (pinfunction "1_1") (pintype "passive"))
      (node (ref "J74") (pin "2") (pinfunction "2_2") (pintype "passive"))
      (node (ref "J74") (pin "3") (pinfunction "3_3") (pintype "passive"))
      (node (ref "J74") (pin "4") (pinfunction "4_4") (pintype "passive"))
      (node (ref "J74") (pin "5") (pinfunction "5_5") (pintype "passive"))
    )
    (net (code "41") (name "Net-(J75-Pad1)") (class "Default")
      (node (ref "J75") (pin "1") (pinfunction "1_1") (pintype "passive"))
      (node (ref "J75") (pin "2") (pinfunction "2_2") (pintype "passive"))
      (node (ref "J75") (pin "3") (pinfunction "3_3") (pintype "passive"))
      (node (ref "J75") (pin "4") (pinfunction "4_4") (pintype "passive"))
      (node (ref "J75") (pin "5") (pinfunction "5_5") (pintype "passive"))
    )
    (net (code "42") (name "Net-(J76-Pad1)") (class "Default")
      (node (ref "J76") (pin "1") (pinfunction "1_1") (pintype "passive"))
      (node (ref "J76") (pin "2") (pinfunction "2_2") (pintype "passive"))
      (node (ref "J76") (pin "3") (pinfunction "3_3") (pintype "passive"))
      (node (ref "J76") (pin "4") (pinfunction "4_4") (pintype "passive"))
      (node (ref "J76") (pin "5") (pinfunction "5_5") (pintype "passive"))
    )
    (net (code "43") (name "Net-(J77-Pad1)") (class "Default")
      (node (ref "J77") (pin "1") (pinfunction "1_1") (pintype "passive"))
      (node (ref "J77") (pin "2") (pinfunction "2_2") (pintype "passive"))
      (node (ref "J77") (pin "3") (pinfunction "3_3") (pintype "passive"))
      (node (ref "J77") (pin "4") (pinfunction "4_4") (pintype "passive"))
      (node (ref "J77") (pin "5") (pinfunction "5_5") (pintype "passive"))
    )
    (net (code "44") (name "Net-(J78-Pad1)") (class "Default")
      (node (ref "J78") (pin "1") (pinfunction "1_1") (pintype "passive"))
      (node (ref "J78") (pin "2") (pinfunction "2_2") (pintype "passive"))
      (node (ref "J78") (pin "3") (pinfunction "3_3") (pintype "passive"))
      (node (ref "J78") (pin "4") (pinfunction "4_4") (pintype "passive"))
      (node (ref "J78") (pin "5") (pinfunction "5_5") (pintype "passive"))
    )
    (net (code "45") (name "Net-(J79-Pad1)") (class "Default")
      (node (ref "J79") (pin "1") (pinfunction "1_1") (pintype "passive"))
      (node (ref "J79") (pin "2") (pinfunction "2_2") (pintype "passive"))
      (node (ref "J79") (pin "3") (pinfunction "3_3") (pintype "passive"))
      (node (ref "J79") (pin "4") (pinfunction "4_4") (pintype "passive"))
      (node (ref "J79") (pin "5") (pinfunction "5_5") (pintype "passive"))
    )
    (net (code "46") (name "Net-(J80-Pad1)") (class "Default")
      (node (ref "J80") (pin "1") (pinfunction "1_1") (pintype "passive"))
      (node (ref "J80") (pin "2") (pinfunction "2_2") (pintype "passive"))
      (node (ref "J80") (pin "3") (pinfunction "3_3") (pintype "passive"))
      (node (ref "J80") (pin "4") (pinfunction "4_4") (pintype "passive"))
      (node (ref "J80") (pin "5") (pinfunction "5_5") (pintype "passive"))
    )
    (net (code "47") (name "Net-(J81-Pad1)") (class "Default")
      (node (ref "J81") (pin "1") (pinfunction "1_1") (pintype "passive"))
      (node (ref "J81") (pin "2") (pinfunction "2_2") (pintype "passive"))
      (node (ref "J81") (pin "3") (pinfunction "3_3") (pintype "passive"))
      (node (ref "J81") (pin "4") (pinfunction "4_4") (pintype "passive"))
      (node (ref "J81") (pin "5") (pinfunction "5_5") (pintype "passive"))
    )
    (net (code "48") (name "Net-(J82-Pad1)") (class "Default")
      (node (ref "J82") (pin "1") (pinfunction "1_1") (pintype "passive"))
      (node (ref "J82") (pin "2") (pinfunction "2_2") (pintype "passive"))
      (node (ref "J82") (pin "3") (pinfunction "3_3") (pintype "passive"))
      (node (ref "J82") (pin "4") (pinfunction "4_4") (pintype "passive"))
      (node (ref "J82") (pin "5") (pinfunction "5_5") (pintype "passive"))
    )
    (net (code "49") (name "Net-(J83-Pad1)") (class "Default")
      (node (ref "J83") (pin "1") (pinfunction "1_1") (pintype "passive"))
      (node (ref "J83") (pin "2") (pinfunction "2_2") (pintype "passive"))
      (node (ref "J83") (pin "3") (pinfunction "3_3") (pintype "passive"))
      (node (ref "J83") (pin "4") (pinfunction "4_4") (pintype "passive"))
      (node (ref "J83") (pin "5") (pinfunction "5_5") (pintype "passive"))
    )
    (net (code "50") (name "Net-(J84-Pad1)") (class "Default")
      (node (ref "J84") (pin "1") (pinfunction "1_1") (pintype "passive"))
      (node (ref "J84") (pin "2") (pinfunction "2_2") (pintype "passive"))
      (node (ref "J84") (pin "3") (pinfunction "3_3") (pintype "passive"))
      (node (ref "J84") (pin "4") (pinfunction "4_4") (pintype "passive"))
      (node (ref "J84") (pin "5") (pinfunction "5_5") (pintype "passive"))
    )
    (net (code "51") (name "Net-(J85-Pad1)") (class "Default")
      (node (ref "J85") (pin "1") (pinfunction "1_1") (pintype "passive"))
      (node (ref "J85") (pin "2") (pinfunction "2_2") (pintype "passive"))
      (node (ref "J85") (pin "3") (pinfunction "3_3") (pintype "passive"))
      (node (ref "J85") (pin "4") (pinfunction "4_4") (pintype "passive"))
      (node (ref "J85") (pin "5") (pinfunction "5_5") (pintype "passive"))
    )
    (net (code "52") (name "Net-(J86-Pad1)") (class "Default")
      (node (ref "J86") (pin "1") (pinfunction "1_1") (pintype "passive"))
      (node (ref "J86") (pin "2") (pinfunction "2_2") (pintype "passive"))
      (node (ref "J86") (pin "3") (pinfunction "3_3") (pintype "passive"))
      (node (ref "J86") (pin "4") (pinfunction "4_4") (pintype "passive"))
      (node (ref "J86") (pin "5") (pinfunction "5_5") (pintype "passive"))
    )
    (net (code "53") (name "Net-(J87-Pad1)") (class "Default")
      (node (ref "J87") (pin "1") (pinfunction "1_1") (pintype "passive"))
      (node (ref "J87") (pin "2") (pinfunction "2_2") (pintype "passive"))
      (node (ref "J87") (pin "3") (pinfunction "3_3") (pintype "passive"))
      (node (ref "J87") (pin "4") (pinfunction "4_4") (pintype "passive"))
      (node (ref "J87") (pin "5") (pinfunction "5_5") (pintype "passive"))
    )
    (net (code "54") (name "Net-(J96-Pad1)") (class "Default")
      (node (ref "J96") (pin "1") (pinfunction "1_1") (pintype "passive"))
      (node (ref "J96") (pin "2") (pinfunction "2_2") (pintype "passive"))
      (node (ref "J96") (pin "3") (pinfunction "3_3") (pintype "passive"))
      (node (ref "J96") (pin "4") (pinfunction "4_4") (pintype "passive"))
      (node (ref "J96") (pin "5") (pinfunction "5_5") (pintype "passive"))
    )
    (net (code "55") (name "Net-(J97-Pad1)") (class "Default")
      (node (ref "J97") (pin "1") (pinfunction "1_1") (pintype "passive"))
      (node (ref "J97") (pin "2") (pinfunction "2_2") (pintype "passive"))
      (node (ref "J97") (pin "3") (pinfunction "3_3") (pintype "passive"))
      (node (ref "J97") (pin "4") (pinfunction "4_4") (pintype "passive"))
      (node (ref "J97") (pin "5") (pinfunction "5_5") (pintype "passive"))
    )
    (net (code "56") (name "Net-(J98-Pad1)") (class "Default")
      (node (ref "J98") (pin "1") (pinfunction "1_1") (pintype "passive"))
      (node (ref "J98") (pin "2") (pinfunction "2_2") (pintype "passive"))
      (node (ref "J98") (pin "3") (pinfunction "3_3") (pintype "passive"))
      (node (ref "J98") (pin "4") (pinfunction "4_4") (pintype "passive"))
      (node (ref "J98") (pin "5") (pinfunction "5_5") (pintype "passive"))
    )
    (net (code "57") (name "Net-(J99-Pad1)") (class "Default")
      (node (ref "J99") (pin "1") (pinfunction "1_1") (pintype "passive"))
      (node (ref "J99") (pin "2") (pinfunction "2_2") (pintype "passive"))
      (node (ref "J99") (pin "3") (pinfunction "3_3") (pintype "passive"))
      (node (ref "J99") (pin "4") (pinfunction "4_4") (pintype "passive"))
      (node (ref "J99") (pin "5") (pinfunction "5_5") (pintype "passive"))
    )
    (net (code "58") (name "Net-(J100-Pad1)") (class "Default")
      (node (ref "J100") (pin "1") (pinfunction "1_1") (pintype "passive"))
      (node (ref "J100") (pin "2") (pinfunction "2_2") (pintype "passive"))
      (node (ref "J100") (pin "3") (pinfunction "3_3") (pintype "passive"))
      (node (ref "J100") (pin "4") (pinfunction "4_4") (pintype "passive"))
      (node (ref "J100") (pin "5") (pinfunction "5_5") (pintype "passive"))
    )
    (net (code "59") (name "Net-(J101-Pad1)") (class "Default")
      (node (ref "J101") (pin "1") (pinfunction "1_1") (pintype "passive"))
      (node (ref "J101") (pin "2") (pinfunction "2_2") (pintype "passive"))
      (node (ref "J101") (pin "3") (pinfunction "3_3") (pintype "passive"))
      (node (ref "J101") (pin "4") (pinfunction "4_4") (pintype "passive"))
      (node (ref "J101") (pin "5") (pinfunction "5_5") (pintype "passive"))
    )
    (net (code "60") (name "Net-(J102-Pad1)") (class "Default")
      (node (ref "J102") (pin "1") (pinfunction "1_1") (pintype "passive"))
      (node (ref "J102") (pin "2") (pinfunction "2_2") (pintype "passive"))
      (node (ref "J102") (pin "3") (pinfunction "3_3") (pintype "passive"))
      (node (ref "J102") (pin "4") (pinfunction "4_4") (pintype "passive"))
      (node (ref "J102") (pin "5") (pinfunction "5_5") (pintype "passive"))
    )
    (net (code "61") (name "Net-(J103-Pad1)") (class "Default")
      (node (ref "J103") (pin "1") (pinfunction "1_1") (pintype "passive"))
      (node (ref "J103") (pin "2") (pinfunction "2_2") (pintype "passive"))
      (node (ref "J103") (pin "3") (pinfunction "3_3") (pintype "passive"))
      (node (ref "J103") (pin "4") (pinfunction "4_4") (pintype "passive"))
      (node (ref "J103") (pin "5") (pinfunction "5_5") (pintype "passive"))
    )
    (net (code "62") (name "Net-(J104-Pad1)") (class "Default")
      (node (ref "J104") (pin "1") (pinfunction "1_1") (pintype "passive"))
      (node (ref "J104") (pin "2") (pinfunction "2_2") (pintype "passive"))
      (node (ref "J104") (pin "3") (pinfunction "3_3") (pintype "passive"))
      (node (ref "J104") (pin "4") (pinfunction "4_4") (pintype "passive"))
      (node (ref "J104") (pin "5") (pinfunction "5_5") (pintype "passive"))
    )
    (net (code "63") (name "Net-(J105-Pad1)") (class "Default")
      (node (ref "J105") (pin "1") (pinfunction "1_1") (pintype "passive"))
      (node (ref "J105") (pin "2") (pinfunction "2_2") (pintype "passive"))
      (node (ref "J105") (pin "3") (pinfunction "3_3") (pintype "passive"))
      (node (ref "J105") (pin "4") (pinfunction "4_4") (pintype "passive"))
      (node (ref "J105") (pin "5") (pinfunction "5_5") (pintype "passive"))
    )
    (net (code "64") (name "Net-(J106-Pad1)") (class "Default")
      (node (ref "J106") (pin "1") (pinfunction "1_1") (pintype "passive"))
      (node (ref "J106") (pin "2") (pinfunction "2_2") (pintype "passive"))
      (node (ref "J106") (pin "3") (pinfunction "3_3") (pintype "passive"))
      (node (ref "J106") (pin "4") (pinfunction "4_4") (pintype "passive"))
      (node (ref "J106") (pin "5") (pinfunction "5_5") (pintype "passive"))
    )
    (net (code "65") (name "Net-(J107-Pad1)") (class "Default")
      (node (ref "J107") (pin "1") (pinfunction "1_1") (pintype "passive"))
      (node (ref "J107") (pin "2") (pinfunction "2_2") (pintype "passive"))
      (node (ref "J107") (pin "3") (pinfunction "3_3") (pintype "passive"))
      (node (ref "J107") (pin "4") (pinfunction "4_4") (pintype "passive"))
      (node (ref "J107") (pin "5") (pinfunction "5_5") (pintype "passive"))
    )
    (net (code "66") (name "Net-(J108-Pad1)") (class "Default")
      (node (ref "J108") (pin "1") (pinfunction "1_1") (pintype "passive"))
      (node (ref "J108") (pin "2") (pinfunction "2_2") (pintype "passive"))
      (node (ref "J108") (pin "3") (pinfunction "3_3") (pintype "passive"))
      (node (ref "J108") (pin "4") (pinfunction "4_4") (pintype "passive"))
      (node (ref "J108") (pin "5") (pinfunction "5_5") (pintype "passive"))
    )
    (net (code "67") (name "Net-(J109-Pad1)") (class "Default")
      (node (ref "J109") (pin "1") (pinfunction "1_1") (pintype "passive"))
      (node (ref "J109") (pin "2") (pinfunction "2_2") (pintype "passive"))
      (node (ref "J109") (pin "3") (pinfunction "3_3") (pintype "passive"))
      (node (ref "J109") (pin "4") (pinfunction "4_4") (pintype "passive"))
      (node (ref "J109") (pin "5") (pinfunction "5_5") (pintype "passive"))
    )
    (net (code "68") (name "Net-(J110-Pad1)") (class "Default")
      (node (ref "J110") (pin "1") (pinfunction "1_1") (pintype "passive"))
      (node (ref "J110") (pin "2") (pinfunction "2_2") (pintype "passive"))
      (node (ref "J110") (pin "3") (pinfunction "3_3") (pintype "passive"))
      (node (ref "J110") (pin "4") (pinfunction "4_4") (pintype "passive"))
      (node (ref "J110") (pin "5") (pinfunction "5_5") (pintype "passive"))
    )
    (net (code "69") (name "Net-(J111-Pad1)") (class "Default")
      (node (ref "J111") (pin "1") (pinfunction "1_1") (pintype "passive"))
      (node (ref "J111") (pin "2") (pinfunction "2_2") (pintype "passive"))
      (node (ref "J111") (pin "3") (pinfunction "3_3") (pintype "passive"))
      (node (ref "J111") (pin "4") (pinfunction "4_4") (pintype "passive"))
      (node (ref "J111") (pin "5") (pinfunction "5_5") (pintype "passive"))
    )
    (net (code "70") (name "Net-(J112-Pad1)") (class "Default")
      (node (ref "J112") (pin "1") (pinfunction "1_1") (pintype "passive"))
      (node (ref "J112") (pin "2") (pinfunction "2_2") (pintype "passive"))
      (node (ref "J112") (pin "3") (pinfunction "3_3") (pintype "passive"))
      (node (ref "J112") (pin "4") (pinfunction "4_4") (pintype "passive"))
      (node (ref "J112") (pin "5") (pinfunction "5_5") (pintype "passive"))
    )
    (net (code "71") (name "Net-(J113-Pad1)") (class "Default")
      (node (ref "J113") (pin "1") (pinfunction "1_1") (pintype "passive"))
      (node (ref "J113") (pin "2") (pinfunction "2_2") (pintype "passive"))
      (node (ref "J113") (pin "3") (pinfunction "3_3") (pintype "passive"))
      (node (ref "J113") (pin "4") (pinfunction "4_4") (pintype "passive"))
      (node (ref "J113") (pin "5") (pinfunction "5_5") (pintype "passive"))
    )
    (net (code "72") (name "Net-(J114-Pad1)") (class "Default")
      (node (ref "J114") (pin "1") (pinfunction "1_1") (pintype "passive"))
      (node (ref "J114") (pin "2") (pinfunction "2_2") (pintype "passive"))
      (node (ref "J114") (pin "3") (pinfunction "3_3") (pintype "passive"))
      (node (ref "J114") (pin "4") (pinfunction "4_4") (pintype "passive"))
      (node (ref "J114") (pin "5") (pinfunction "5_5") (pintype "passive"))
    )
    (net (code "73") (name "Net-(J115-Pad1)") (class "Default")
      (node (ref "J115") (pin "1") (pinfunction "1_1") (pintype "passive"))
      (node (ref "J115") (pin "2") (pinfunction "2_2") (pintype "passive"))
      (node (ref "J115") (pin "3") (pinfunction "3_3") (pintype "passive"))
      (node (ref "J115") (pin "4") (pinfunction "4_4") (pintype "passive"))
      (node (ref "J115") (pin "5") (pinfunction "5_5") (pintype "passive"))
    )
    (net (code "74") (name "Net-(J116-Pad1)") (class "Default")
      (node (ref "J116") (pin "1") (pinfunction "1_1") (pintype "passive"))
      (node (ref "J116") (pin "2") (pinfunction "2_2") (pintype "passive"))
      (node (ref "J116") (pin "3") (pinfunction "3_3") (pintype "passive"))
      (node (ref "J116") (pin "4") (pinfunction "4_4") (pintype "passive"))
      (node (ref "J116") (pin "5") (pinfunction "5_5") (pintype "passive"))
    )
    (net (code "75") (name "Net-(J117-Pad1)") (class "Default")
      (node (ref "J117") (pin "1") (pinfunction "1_1") (pintype "passive"))
      (node (ref "J117") (pin "2") (pinfunction "2_2") (pintype "passive"))
      (node (ref "J117") (pin "3") (pinfunction "3_3") (pintype "passive"))
      (node (ref "J117") (pin "4") (pinfunction "4_4") (pintype "passive"))
      (node (ref "J117") (pin "5") (pinfunction "5_5") (pintype "passive"))
    )
    (net (code "76") (name "Net-(J118-Pad1)") (class "Default")
      (node (ref "J118") (pin "1") (pinfunction "1_1") (pintype "passive"))
      (node (ref "J118") (pin "2") (pinfunction "2_2") (pintype "passive"))
      (node (ref "J118") (pin "3") (pinfunction "3_3") (pintype "passive"))
      (node (ref "J118") (pin "4") (pinfunction "4_4") (pintype "passive"))
      (node (ref "J118") (pin "5") (pinfunction "5_5") (pintype "passive"))
    )
    (net (code "77") (name "Net-(J119-Pad1)") (class "Default")
      (node (ref "J119") (pin "1") (pinfunction "1_1") (pintype "passive"))
      (node (ref "J119") (pin "2") (pinfunction "2_2") (pintype "passive"))
      (node (ref "J119") (pin "3") (pinfunction "3_3") (pintype "passive"))
      (node (ref "J119") (pin "4") (pinfunction "4_4") (pintype "passive"))
      (node (ref "J119") (pin "5") (pinfunction "5_5") (pintype "passive"))
    )
    (net (code "78") (name "Net-(J120-Pad1)") (class "Default")
      (node (ref "J120") (pin "1") (pinfunction "1_1") (pintype "passive"))
      (node (ref "J120") (pin "2") (pinfunction "2_2") (pintype "passive"))
      (node (ref "J120") (pin "3") (pinfunction "3_3") (pintype "passive"))
      (node (ref "J120") (pin "4") (pinfunction "4_4") (pintype "passive"))
      (node (ref "J120") (pin "5") (pinfunction "5_5") (pintype "passive"))
    )
    (net (code "79") (name "Net-(J121-Pad1)") (class "Default")
      (node (ref "J121") (pin "1") (pinfunction "1_1") (pintype "passive"))
      (node (ref "J121") (pin "2") (pinfunction "2_2") (pintype "passive"))
      (node (ref "J121") (pin "3") (pinfunction "3_3") (pintype "passive"))
      (node (ref "J121") (pin "4") (pinfunction "4_4") (pintype "passive"))
      (node (ref "J121") (pin "5") (pinfunction "5_5") (pintype "passive"))
    )
    (net (code "80") (name "Net-(J122-Pad1)") (class "Default")
      (node (ref "J122") (pin "1") (pinfunction "1_1") (pintype "passive"))
      (node (ref "J122") (pin "2") (pinfunction "2_2") (pintype "passive"))
      (node (ref "J122") (pin "3") (pinfunction "3_3") (pintype "passive"))
      (node (ref "J122") (pin "4") (pinfunction "4_4") (pintype "passive"))
      (node (ref "J122") (pin "5") (pinfunction "5_5") (pintype "passive"))
    )
  )
)
